# CATS-EUROC-Frontend.net
KiCad netlist of a schematic drawn in Altium Designer
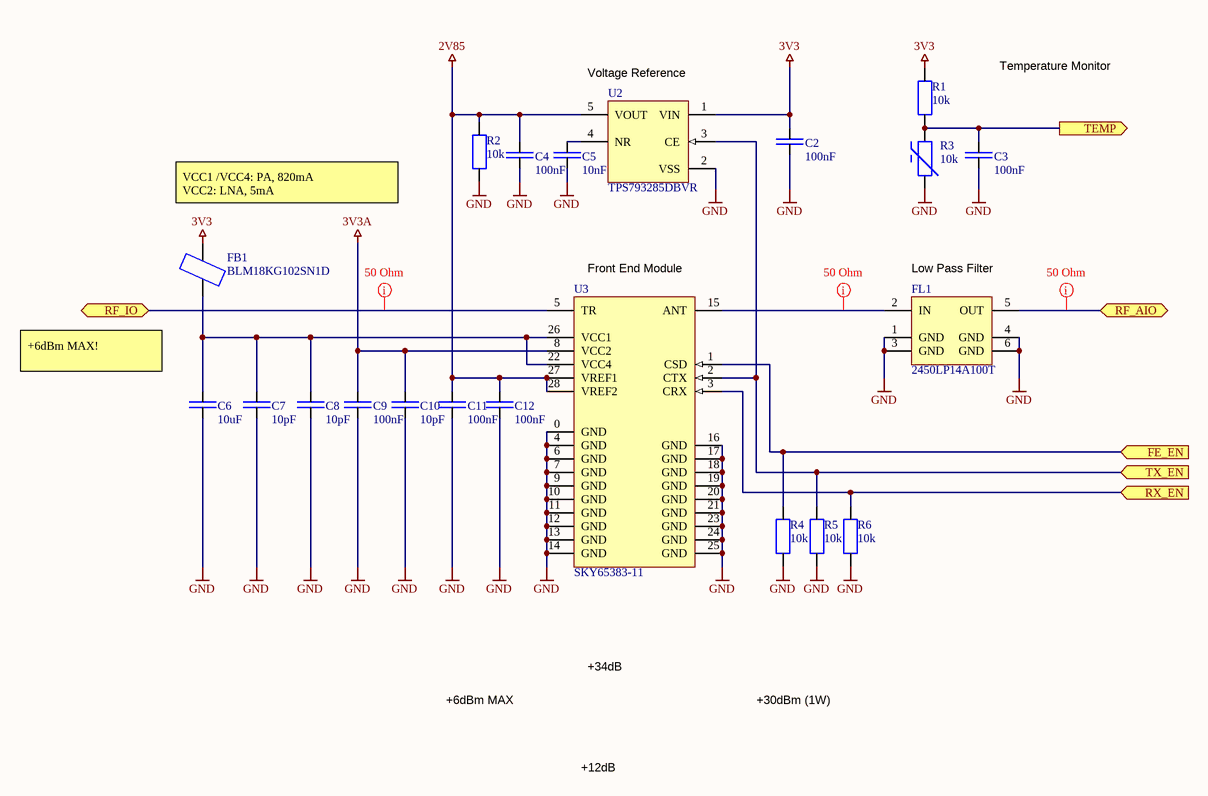
[diagram p0: CATS-EUROC-Frontend.SchDoc]

(export (version "E")
  (design (tool "Eeschema 10.0.6"))
  (components
    (comp (ref "C2")
      (value "100nF")
      (footprint "SMD Keramikkondensator 0402")
      (description "SMD Ceramic Capacitor E6")
      (libsource (lib "CATS-EUROC") (part "E6 - 100nF"))
    )
    (comp (ref "C3")
      (value "100nF")
      (footprint "SMD Keramikkondensator 0402")
      (description "SMD Ceramic Capacitor E6")
      (libsource (lib "CATS-EUROC") (part "E6 - 100nF"))
    )
    (comp (ref "C4")
      (value "100nF")
      (footprint "SMD Keramikkondensator 0402")
      (description "SMD Ceramic Capacitor E6")
      (libsource (lib "CATS-EUROC") (part "E6 - 100nF"))
    )
    (comp (ref "C5")
      (value "10nF")
      (footprint "SMD Keramikkondensator 0402")
      (description "SMD Ceramic Capacitor E6")
      (libsource (lib "CATS-EUROC") (part "E6 - 10nF"))
    )
    (comp (ref "C6")
      (value "10uF")
      (footprint "SMD Keramikkondensator 0603")
      (description "SMD Ceramic Capacitor E6")
      (libsource (lib "CATS-EUROC") (part "E6 - 10uF"))
    )
    (comp (ref "C7")
      (value "10pF")
      (footprint "SMD Keramikkondensator 0402")
      (description "SMD Ceramic Capacitor E6")
      (libsource (lib "CATS-EUROC") (part "E6 - 10pF"))
    )
    (comp (ref "C8")
      (value "10pF")
      (footprint "SMD Keramikkondensator 0402")
      (description "SMD Ceramic Capacitor E6")
      (libsource (lib "CATS-EUROC") (part "E6 - 10pF"))
    )
    (comp (ref "C9")
      (value "100nF")
      (footprint "SMD Keramikkondensator 0402")
      (description "SMD Ceramic Capacitor E6")
      (libsource (lib "CATS-EUROC") (part "E6 - 100nF"))
    )
    (comp (ref "C10")
      (value "10pF")
      (footprint "SMD Keramikkondensator 0402")
      (description "SMD Ceramic Capacitor E6")
      (libsource (lib "CATS-EUROC") (part "E6 - 10pF"))
    )
    (comp (ref "C11")
      (value "100nF")
      (footprint "SMD Keramikkondensator 0402")
      (description "SMD Ceramic Capacitor E6")
      (libsource (lib "CATS-EUROC") (part "E6 - 100nF"))
    )
    (comp (ref "C12")
      (value "100nF")
      (footprint "SMD Keramikkondensator 0402")
      (description "SMD Ceramic Capacitor E6")
      (libsource (lib "CATS-EUROC") (part "E6 - 100nF"))
    )
    (comp (ref "FB1")
      (value "BLM18KG102SN1D")
      (footprint "SMD Ferrite Bead 0603")
      (description "1 kOhms @ 100MHz 1 Power Line Ferrite Bead 0603 (1608 Metric) 1A 200mOhm")
      (libsource (lib "CATS-EUROC") (part "BLM18KG102SN1D"))
    )
    (comp (ref "FL1")
      (value "2450LP14A100T")
      (footprint "SMD Filter 2450LP14A100T")
      (libsource (lib "RF") (part "2450LP14A100T"))
    )
    (comp (ref "R1")
      (value "10k")
      (footprint "SMD Widerstand 0402")
      (description "SMD Chip Resistor E24")
      (libsource (lib "CATS-EUROC") (part "E24 - 10k"))
    )
    (comp (ref "R2")
      (value "10k")
      (footprint "SMD Widerstand 0402")
      (description "SMD Chip Resistor E24")
      (libsource (lib "CATS-EUROC") (part "E24 - 10k"))
    )
    (comp (ref "R3")
      (value "10k")
      (footprint "SMD Ferrite Bead 0402")
      (description "10kΩ -40℃~+125℃ 3455K 0.1mA 3434K ±1% 3380K ±1% 0402 NTC Thermistors")
      (libsource (lib "Sensors") (part "NCU15XH103F6SRC"))
    )
    (comp (ref "R4")
      (value "10k")
      (footprint "SMD Widerstand 0402")
      (description "SMD Chip Resistor E24")
      (libsource (lib "CATS-EUROC") (part "E24 - 10k"))
    )
    (comp (ref "R5")
      (value "10k")
      (footprint "SMD Widerstand 0402")
      (description "SMD Chip Resistor E24")
      (libsource (lib "CATS-EUROC") (part "E24 - 10k"))
    )
    (comp (ref "R6")
      (value "10k")
      (footprint "SMD Widerstand 0402")
      (description "SMD Chip Resistor E24")
      (libsource (lib "CATS-EUROC") (part "E24 - 10k"))
    )
    (comp (ref "U2")
      (value "TPS793285DBVR")
      (footprint "SMD IC SOT-23-5")
      (description "Linear Voltage Regulator IC Positive Fixed 1 Output  200mA SOT-23-5 2.85V")
      (libsource (lib "Voltage-Converter") (part "TPS793285DBVR"))
    )
    (comp (ref "U3")
      (value "SKY65383-11")
      (footprint "SMD IC 28-MCM")
      (description "2400 to 2483 MHz Transmit/Receive\r\nFront-End Module +30dBm")
      (libsource (lib "RF") (part "SKY65383-11"))
    )
  )
  (nets
    (net (code "1") (name "/FE_EN") (class "Default")
      (node (ref "R4") (pin "2") (pinfunction "2_2") (pintype "passive"))
      (node (ref "U3") (pin "1") (pinfunction "CSD_1") (pintype "input"))
    )
    (net (code "2") (name "/RF_AIO") (class "Default")
      (node (ref "FL1") (pin "5") (pinfunction "OUT_5") (pintype "passive"))
    )
    (net (code "3") (name "/RF_IO") (class "Default")
      (node (ref "U3") (pin "5") (pinfunction "TR_5") (pintype "passive"))
    )
    (net (code "4") (name "/RX_EN") (class "Default")
      (node (ref "R6") (pin "2") (pinfunction "2_2") (pintype "passive"))
      (node (ref "U3") (pin "3") (pinfunction "CRX_3") (pintype "input"))
    )
    (net (code "5") (name "/TEMP") (class "Default")
      (node (ref "C3") (pin "2") (pinfunction "2_2") (pintype "passive"))
      (node (ref "R1") (pin "1") (pinfunction "1_1") (pintype "passive"))
      (node (ref "R3") (pin "1") (pinfunction "1_1") (pintype "passive"))
    )
    (net (code "6") (name "/TX_EN") (class "Default")
      (node (ref "R5") (pin "2") (pinfunction "2_2") (pintype "passive"))
      (node (ref "U2") (pin "3") (pinfunction "CE_3") (pintype "input"))
      (node (ref "U3") (pin "2") (pinfunction "CTX_2") (pintype "input"))
    )
    (net (code "7") (name "2V85") (class "Default")
      (node (ref "C11") (pin "2") (pinfunction "2_2") (pintype "passive"))
      (node (ref "C12") (pin "2") (pinfunction "2_2") (pintype "passive"))
      (node (ref "C4") (pin "2") (pinfunction "2_2") (pintype "passive"))
      (node (ref "R2") (pin "2") (pinfunction "2_2") (pintype "passive"))
      (node (ref "U2") (pin "5") (pinfunction "VOUT_5") (pintype "passive"))
      (node (ref "U3") (pin "27") (pinfunction "VREF1_27") (pintype "passive"))
      (node (ref "U3") (pin "28") (pinfunction "VREF2_28") (pintype "passive"))
    )
    (net (code "8") (name "3V3") (class "Default")
      (node (ref "C2") (pin "2") (pinfunction "2_2") (pintype "passive"))
      (node (ref "FB1") (pin "2") (pinfunction "2_2") (pintype "passive"))
      (node (ref "R1") (pin "2") (pinfunction "2_2") (pintype "passive"))
      (node (ref "U2") (pin "1") (pinfunction "VIN_1") (pintype "passive"))
    )
    (net (code "9") (name "3V3A") (class "Default")
      (node (ref "C10") (pin "2") (pinfunction "2_2") (pintype "passive"))
      (node (ref "C9") (pin "2") (pinfunction "2_2") (pintype "passive"))
      (node (ref "U3") (pin "8") (pinfunction "VCC2_8") (pintype "passive"))
    )
    (net (code "10") (name "GND") (class "Default")
      (node (ref "C10") (pin "1") (pinfunction "1_1") (pintype "passive"))
      (node (ref "C11") (pin "1") (pinfunction "1_1") (pintype "passive"))
      (node (ref "C12") (pin "1") (pinfunction "1_1") (pintype "passive"))
      (node (ref "C2") (pin "1") (pinfunction "1_1") (pintype "passive"))
      (node (ref "C3") (pin "1") (pinfunction "1_1") (pintype "passive"))
      (node (ref "C4") (pin "1") (pinfunction "1_1") (pintype "passive"))
      (node (ref "C5") (pin "1") (pinfunction "1_1") (pintype "passive"))
      (node (ref "C6") (pin "1") (pinfunction "1_1") (pintype "passive"))
      (node (ref "C7") (pin "1") (pinfunction "1_1") (pintype "passive"))
      (node (ref "C8") (pin "1") (pinfunction "1_1") (pintype "passive"))
      (node (ref "C9") (pin "1") (pinfunction "1_1") (pintype "passive"))
      (node (ref "FL1") (pin "1") (pinfunction "GND_1") (pintype "passive"))
      (node (ref "FL1") (pin "3") (pinfunction "GND_3") (pintype "passive"))
      (node (ref "FL1") (pin "4") (pinfunction "GND_4") (pintype "passive"))
      (node (ref "FL1") (pin "6") (pinfunction "GND_6") (pintype "passive"))
      (node (ref "R2") (pin "1") (pinfunction "1_1") (pintype "passive"))
      (node (ref "R3") (pin "2") (pinfunction "2_2") (pintype "passive"))
      (node (ref "R4") (pin "1") (pinfunction "1_1") (pintype "passive"))
      (node (ref "R5") (pin "1") (pinfunction "1_1") (pintype "passive"))
      (node (ref "R6") (pin "1") (pinfunction "1_1") (pintype "passive"))
      (node (ref "U2") (pin "2") (pinfunction "VSS_2") (pintype "passive"))
      (node (ref "U3") (pin "0") (pinfunction "GND_0") (pintype "passive"))
      (node (ref "U3") (pin "10") (pinfunction "GND_10") (pintype "passive"))
      (node (ref "U3") (pin "11") (pinfunction "GND_11") (pintype "passive"))
      (node (ref "U3") (pin "12") (pinfunction "GND_12") (pintype "passive"))
      (node (ref "U3") (pin "13") (pinfunction "GND_13") (pintype "passive"))
      (node (ref "U3") (pin "14") (pinfunction "GND_14") (pintype "passive"))
      (node (ref "U3") (pin "16") (pinfunction "GND_16") (pintype "passive"))
      (node (ref "U3") (pin "17") (pinfunction "GND_17") (pintype "passive"))
      (node (ref "U3") (pin "18") (pinfunction "GND_18") (pintype "passive"))
      (node (ref "U3") (pin "19") (pinfunction "GND_19") (pintype "passive"))
      (node (ref "U3") (pin "20") (pinfunction "GND_20") (pintype "passive"))
      (node (ref "U3") (pin "21") (pinfunction "GND_21") (pintype "passive"))
      (node (ref "U3") (pin "23") (pinfunction "GND_23") (pintype "passive"))
      (node (ref "U3") (pin "24") (pinfunction "GND_24") (pintype "passive"))
      (node (ref "U3") (pin "25") (pinfunction "GND_25") (pintype "passive"))
      (node (ref "U3") (pin "4") (pinfunction "GND_4") (pintype "passive"))
      (node (ref "U3") (pin "6") (pinfunction "GND_6") (pintype "passive"))
      (node (ref "U3") (pin "7") (pinfunction "GND_7") (pintype "passive"))
      (node (ref "U3") (pin "9") (pinfunction "GND_9") (pintype "passive"))
    )
    (net (code "11") (name "Net-(FL1-IN)") (class "Default")
      (node (ref "FL1") (pin "2") (pinfunction "IN_2") (pintype "passive"))
      (node (ref "U3") (pin "15") (pinfunction "ANT_15") (pintype "passive"))
    )
    (net (code "12") (name "Net-(U2-NR)") (class "Default")
      (node (ref "C5") (pin "2") (pinfunction "2_2") (pintype "passive"))
      (node (ref "U2") (pin "4") (pinfunction "NR_4") (pintype "passive"))
    )
    (net (code "13") (name "Net-(U3-VCC1)") (class "Default")
      (node (ref "C6") (pin "2") (pinfunction "2_2") (pintype "passive"))
      (node (ref "C7") (pin "2") (pinfunction "2_2") (pintype "passive"))
      (node (ref "C8") (pin "2") (pinfunction "2_2") (pintype "passive"))
      (node (ref "FB1") (pin "1") (pinfunction "1_1") (pintype "passive"))
      (node (ref "U3") (pin "22") (pinfunction "VCC4_22") (pintype "passive"))
      (node (ref "U3") (pin "26") (pinfunction "VCC1_26") (pintype "passive"))
    )
  )
)
